# 2WiresLink_BluePill.net
KiCad netlist of a schematic drawn in EAGLE
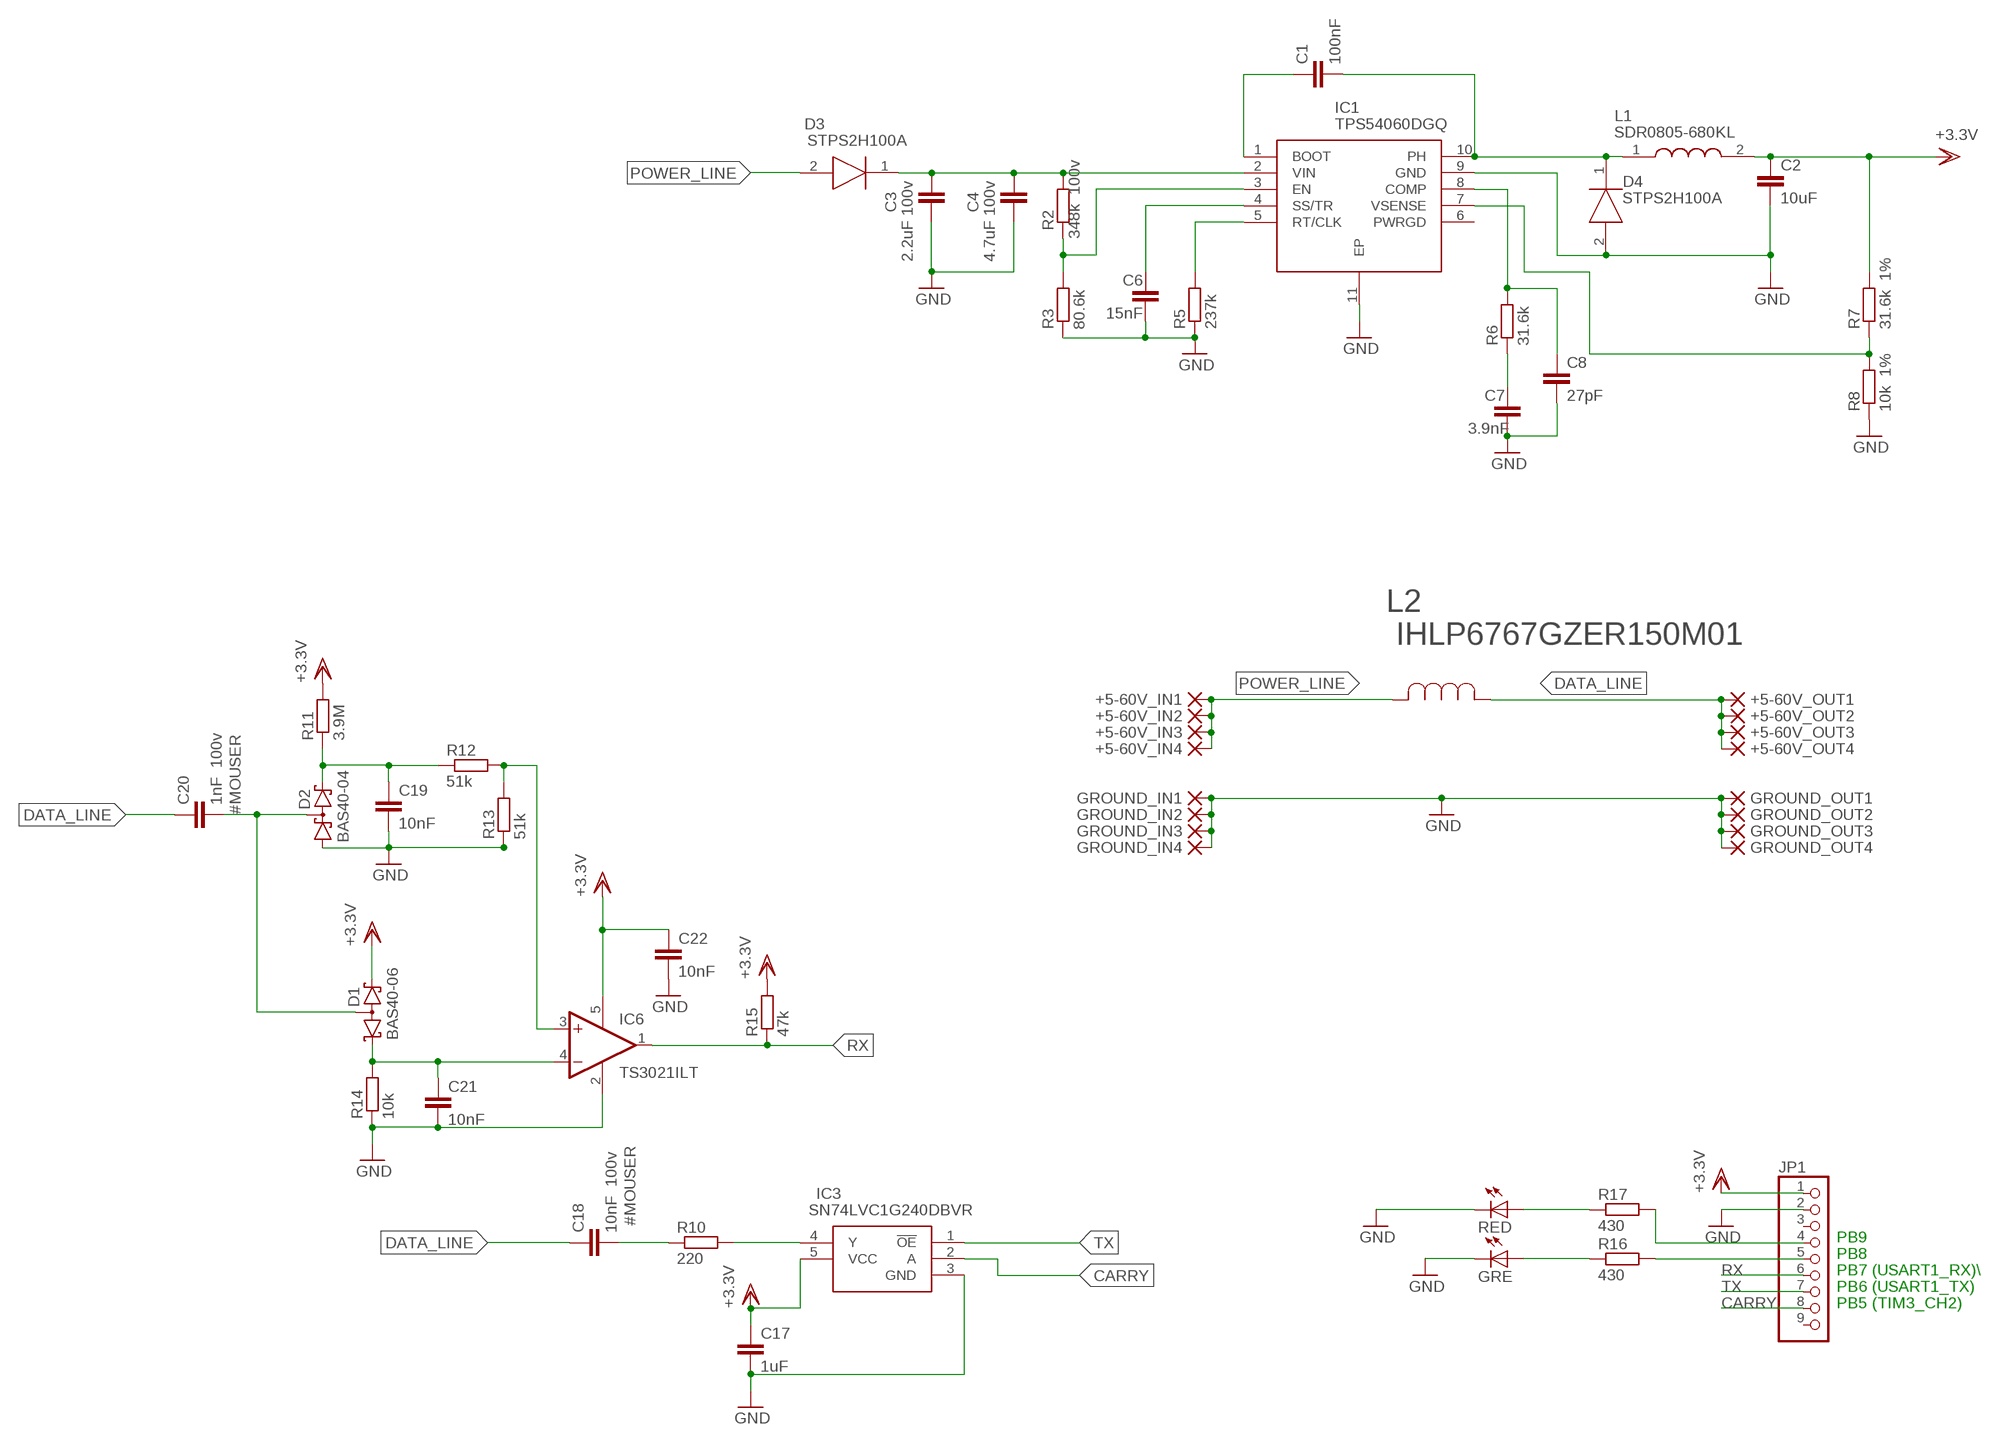
[diagram p0: schematic, sheet 1]

(export (version "E")
  (design (tool "Eeschema 10.0.6"))
  (components
    (comp (ref "+5-60V_IN1")
      (value "PAD-0820-S")
      (footprint "eagle-import:0820-S")
      (libsource (lib "eagle-import") (part "PAD-0820-S"))
    )
    (comp (ref "+5-60V_IN2")
      (value "PAD-0820-S")
      (footprint "eagle-import:0820-S")
      (libsource (lib "eagle-import") (part "PAD-0820-S"))
    )
    (comp (ref "+5-60V_IN3")
      (value "PAD-0820-S")
      (footprint "eagle-import:0820-S")
      (libsource (lib "eagle-import") (part "PAD-0820-S"))
    )
    (comp (ref "+5-60V_IN4")
      (value "PAD-0820-S")
      (footprint "eagle-import:0820-S")
      (libsource (lib "eagle-import") (part "PAD-0820-S"))
    )
    (comp (ref "+5-60V_OUT1")
      (value "PAD-0820-S")
      (footprint "eagle-import:0820-S")
      (libsource (lib "eagle-import") (part "PAD-0820-S"))
    )
    (comp (ref "+5-60V_OUT2")
      (value "PAD-0820-S")
      (footprint "eagle-import:0820-S")
      (libsource (lib "eagle-import") (part "PAD-0820-S"))
    )
    (comp (ref "+5-60V_OUT3")
      (value "PAD-0820-S")
      (footprint "eagle-import:0820-S")
      (libsource (lib "eagle-import") (part "PAD-0820-S"))
    )
    (comp (ref "+5-60V_OUT4")
      (value "PAD-0820-S")
      (footprint "eagle-import:0820-S")
      (libsource (lib "eagle-import") (part "PAD-0820-S"))
    )
    (comp (ref "C1")
      (value "100nF")
      (footprint "eagle-import:C0603")
      (fields (field (name "MF") "KEMET") (field (name "MPN") "C0603C104K5RECAUTO"))
      (libsource (lib "eagle-import") (part "C-EUC0603"))
    )
    (comp (ref "C2")
      (value "10uF")
      (footprint "eagle-import:C0603")
      (fields (field (name "MF") "Murata Electronics") (field (name "MPN") "GRM188R61A106KE69D"))
      (libsource (lib "eagle-import") (part "C-EUC0603"))
    )
    (comp (ref "C3")
      (value "2.2uF 100v")
      (footprint "eagle-import:C1210")
      (fields (field (name "MF") "TDK") (field (name "MPN") "C3225X7R2A225K230AB"))
      (libsource (lib "eagle-import") (part "C-EUC1210"))
    )
    (comp (ref "C4")
      (value "4.7uF 100v")
      (footprint "eagle-import:C1210")
      (fields (field (name "MF") "TDK") (field (name "MPN") "CGA6M3X7S2A475K200AB"))
      (libsource (lib "eagle-import") (part "C-EUC1210"))
    )
    (comp (ref "C6")
      (value "15nF")
      (footprint "eagle-import:C0603")
      (fields (field (name "MF") "KEMET") (field (name "MPN") "C0603C153K5RACTU"))
      (libsource (lib "eagle-import") (part "C-EUC0603"))
    )
    (comp (ref "C7")
      (value "3.9nF")
      (footprint "eagle-import:C0603")
      (fields (field (name "MF") "Murata Electronics") (field (name "MPN") "GCM1885C1H392JA16D"))
      (libsource (lib "eagle-import") (part "C-EUC0603"))
    )
    (comp (ref "C8")
      (value "27pF")
      (footprint "eagle-import:C0603")
      (fields (field (name "MF") "AVX") (field (name "MPN") "06035A270JAT2A"))
      (libsource (lib "eagle-import") (part "C-EUC0603"))
    )
    (comp (ref "C17")
      (value "1uF")
      (footprint "eagle-import:C0603")
      (fields (field (name "MF") "AVX") (field (name "MPN") "0603YD105KAT2A"))
      (libsource (lib "eagle-import") (part "C-EUC0603"))
    )
    (comp (ref "C18")
      (value "10nF 100v")
      (footprint "eagle-import:C0603")
      (fields (field (name "MF") "Murata Electronics") (field (name "MPN") "GCM188R72A103KA37D"))
      (libsource (lib "eagle-import") (part "C-EUC0603"))
    )
    (comp (ref "C19")
      (value "10nF")
      (footprint "eagle-import:C0603")
      (fields (field (name "MF") "KEMET") (field (name "MPN") "C0603C103K5RACAUTO7411"))
      (libsource (lib "eagle-import") (part "C-EUC0603"))
    )
    (comp (ref "C20")
      (value "1nF 100v")
      (footprint "eagle-import:C0603")
      (fields (field (name "MF") "AVX") (field (name "MPN") "06031C102KAT2A"))
      (libsource (lib "eagle-import") (part "C-EUC0603"))
    )
    (comp (ref "C21")
      (value "10nF")
      (footprint "eagle-import:C0603")
      (fields (field (name "MF") "KEMET"))
      (libsource (lib "eagle-import") (part "C-EUC0603"))
    )
    (comp (ref "C22")
      (value "10nF")
      (footprint "eagle-import:C0603")
      (fields (field (name "MF") "KEMET") (field (name "MPN") "C0603C103K5RACAUTO7411"))
      (libsource (lib "eagle-import") (part "C-EUC0603"))
    )
    (comp (ref "D1")
      (value "BAS40-06")
      (footprint "eagle-import:SOT23")
      (fields (field (name "MF") "Vishay Semiconductors") (field (name "MPN") "BAS40-06-E3-08"))
      (libsource (lib "eagle-import") (part "BAS40-06"))
    )
    (comp (ref "D2")
      (value "BAS40-04")
      (footprint "eagle-import:SOT23")
      (fields (field (name "MF") "Diodes Incorporated") (field (name "MPN") "BAS40-04-7-F"))
      (libsource (lib "eagle-import") (part "BAS40-04"))
    )
    (comp (ref "D3")
      (value "STPS2H100A")
      (footprint "eagle-import:DIOM5126X265N")
      (fields (field (name "MOUSER_PART_NUMBER") "511-STPS2H100A") (field (name "MF") "STMicroelectronics"))
      (libsource (lib "eagle-import") (part "STPS2H100A"))
    )
    (comp (ref "D4")
      (value "STPS2H100A")
      (footprint "eagle-import:DIOM5126X265N")
      (fields (field (name "MOUSER_PART_NUMBER") "511-STPS2H100A") (field (name "MF") "STMicroelectronics"))
      (libsource (lib "eagle-import") (part "STPS2H100A"))
    )
    (comp (ref "GRE")
      (value "GRE")
      (footprint "eagle-import:CHIP-LED0805")
      (fields (field (name "MF") "Lumex") (field (name "MPN") "SML-LXT0805GW-TR"))
      (libsource (lib "eagle-import") (part "LEDCHIP-LED0805"))
    )
    (comp (ref "GROUND_IN1")
      (value "PAD-0820-S")
      (footprint "eagle-import:0820-S")
      (libsource (lib "eagle-import") (part "PAD-0820-S"))
    )
    (comp (ref "GROUND_IN2")
      (value "PAD-0820-S")
      (footprint "eagle-import:0820-S")
      (libsource (lib "eagle-import") (part "PAD-0820-S"))
    )
    (comp (ref "GROUND_IN3")
      (value "PAD-0820-S")
      (footprint "eagle-import:0820-S")
      (libsource (lib "eagle-import") (part "PAD-0820-S"))
    )
    (comp (ref "GROUND_IN4")
      (value "PAD-0820-S")
      (footprint "eagle-import:0820-S")
      (libsource (lib "eagle-import") (part "PAD-0820-S"))
    )
    (comp (ref "GROUND_OUT1")
      (value "PAD-0820-S")
      (footprint "eagle-import:0820-S")
      (libsource (lib "eagle-import") (part "PAD-0820-S"))
    )
    (comp (ref "GROUND_OUT2")
      (value "PAD-0820-S")
      (footprint "eagle-import:0820-S")
      (libsource (lib "eagle-import") (part "PAD-0820-S"))
    )
    (comp (ref "GROUND_OUT3")
      (value "PAD-0820-S")
      (footprint "eagle-import:0820-S")
      (libsource (lib "eagle-import") (part "PAD-0820-S"))
    )
    (comp (ref "GROUND_OUT4")
      (value "PAD-0820-S")
      (footprint "eagle-import:0820-S")
      (libsource (lib "eagle-import") (part "PAD-0820-S"))
    )
    (comp (ref "IC1")
      (value "TPS54060DGQ")
      (footprint "eagle-import:SOP50P490X110-11N")
      (fields
        (field (name "MOUSER_PART_NUMBER") "595-TPS54060DGQ")
        (field (name "MF") "Texas Instruments")
        (field (name "MPN") "TPS54060DGQR")
      )
      (libsource (lib "eagle-import") (part "TPS54060DGQ"))
    )
    (comp (ref "IC3")
      (value "SN74LVC1G240DBVR")
      (footprint "eagle-import:SOT95P280X145-5N")
      (fields
        (field (name "MOUSER_PART_NUMBER") "595-SN74LVC1G240DBVR")
        (field (name "MF") "Texas Instruments")
      )
      (libsource (lib "eagle-import") (part "SN74LVC1G240DBVR"))
    )
    (comp (ref "IC6")
      (value "TS3021ILT")
      (footprint "eagle-import:SOT95P280X145-5N")
      (fields (field (name "MF") "STMicroelectronics"))
      (libsource (lib "eagle-import") (part "TS3021ILT"))
    )
    (comp (ref "JP1")
      (value "PINHD-1X9")
      (footprint "eagle-import:1X09-BIG")
      (libsource (lib "eagle-import") (part "PINHD-1X9"))
    )
    (comp (ref "L1")
      (value "SDR0805-680KL")
      (footprint "eagle-import:SDR0805-680KL")
      (fields (field (name "MOUSER_PART_NUMBER") "652-SDR0805-680KL") (field (name "MF") "Bourns"))
      (libsource (lib "eagle-import") (part "SDR0805-680KL"))
    )
    (comp (ref "L2")
      (value "IHLP6767GZER150M01")
      (footprint "eagle-import:IND_IHLP-6767GZ")
      (fields (field (name "MF") "Vishay / Dale"))
      (libsource (lib "eagle-import") (part "IHLP6767GZER150M01"))
    )
    (comp (ref "R2")
      (value "348k 100v")
      (footprint "eagle-import:R0603")
      (fields (field (name "MF") "Susumu") (field (name "MPN") "RG1608P-3483-D-T5"))
      (libsource (lib "eagle-import") (part "R-EU_R0603"))
    )
    (comp (ref "R3")
      (value "80.6k")
      (footprint "eagle-import:R0603")
      (fields (field (name "MF") "Vishay / Dale") (field (name "MPN") "CRCW060380K6FKEA"))
      (libsource (lib "eagle-import") (part "R-EU_R0603"))
    )
    (comp (ref "R5")
      (value "237k")
      (footprint "eagle-import:R0603")
      (fields (field (name "MF") "Yageo") (field (name "MPN") "AC0603FR-07237KL"))
      (libsource (lib "eagle-import") (part "R-EU_R0603"))
    )
    (comp (ref "R6")
      (value "31.6k")
      (footprint "eagle-import:R0603")
      (fields (field (name "MF") "Yageo") (field (name "MPN") "AC0603FR-0731K6L"))
      (libsource (lib "eagle-import") (part "R-EU_R0603"))
    )
    (comp (ref "R7")
      (value "31.6k 1%")
      (footprint "eagle-import:R0603")
      (fields (field (name "MF") "Yageo") (field (name "MPN") "AC0603FR-0731K6L"))
      (libsource (lib "eagle-import") (part "R-EU_R0603"))
    )
    (comp (ref "R8")
      (value "10k 1%")
      (footprint "eagle-import:R0603")
      (fields (field (name "MF") "Vishay / Dale") (field (name "MPN") "CRCW060310K0FKEAC"))
      (libsource (lib "eagle-import") (part "R-EU_R0603"))
    )
    (comp (ref "R10")
      (value "220")
      (footprint "eagle-import:R0603")
      (fields (field (name "MF") "Yageo") (field (name "MPN") "RC0603FR-07220RL"))
      (libsource (lib "eagle-import") (part "R-EU_R0603"))
    )
    (comp (ref "R11")
      (value "3.9M")
      (footprint "eagle-import:R0603")
      (fields (field (name "MF") "Yageo") (field (name "MPN") "RC0603FR-073M9L"))
      (libsource (lib "eagle-import") (part "R-EU_R0603"))
    )
    (comp (ref "R12")
      (value "51k")
      (footprint "eagle-import:R0603")
      (fields (field (name "MF") "Yageo") (field (name "MPN") "RC0603FR-0751KL"))
      (libsource (lib "eagle-import") (part "R-EU_R0603"))
    )
    (comp (ref "R13")
      (value "51k")
      (footprint "eagle-import:R0603")
      (fields (field (name "MF") "Yageo") (field (name "MPN") "RC0603FR-0751KL"))
      (libsource (lib "eagle-import") (part "R-EU_R0603"))
    )
    (comp (ref "R14")
      (value "10k")
      (footprint "eagle-import:R0603")
      (fields (field (name "MF") "Vishay / Dale") (field (name "MPN") "CRCW060310K0FKEAC"))
      (libsource (lib "eagle-import") (part "R-EU_R0603"))
    )
    (comp (ref "R15")
      (value "47k")
      (footprint "eagle-import:R0603")
      (fields (field (name "MF") "Yageo") (field (name "MPN") "RC0603FR-0747KL"))
      (libsource (lib "eagle-import") (part "R-EU_R0603"))
    )
    (comp (ref "R16")
      (value "430")
      (footprint "eagle-import:R0603")
      (fields (field (name "MF") "Yageo") (field (name "MPN") "RC0603FR-07430RL"))
      (libsource (lib "eagle-import") (part "R-EU_R0603"))
    )
    (comp (ref "R17")
      (value "430")
      (footprint "eagle-import:R0603")
      (fields (field (name "MF") "Yageo") (field (name "MPN") "RC0603FR-07430RL"))
      (libsource (lib "eagle-import") (part "R-EU_R0603"))
    )
    (comp (ref "RED")
      (value "RED")
      (footprint "eagle-import:CHIP-LED0805")
      (fields (field (name "MF") "Lumex") (field (name "MPN") "SML-LXT0805IW-TR"))
      (libsource (lib "eagle-import") (part "LEDCHIP-LED0805"))
    )
  )
  (nets
    (net (code "1") (name "+3.3V") (class "Default")
      (node (ref "C17") (pin "1") (pinfunction "1_1") (pintype "passive"))
      (node (ref "C2") (pin "1") (pinfunction "1_1") (pintype "passive"))
      (node (ref "C22") (pin "1") (pinfunction "1_1") (pintype "passive"))
      (node (ref "D1") (pin "2") (pinfunction "K2_2") (pintype "passive"))
      (node (ref "IC3") (pin "5") (pinfunction "VCC_5") (pintype "power_in"))
      (node (ref "IC6") (pin "5") (pinfunction "V+_5") (pintype "power_in"))
      (node (ref "JP1") (pin "1") (pinfunction "1_1") (pintype "passive"))
      (node (ref "L1") (pin "2") (pinfunction "2_2") (pintype "bidirectional"))
      (node (ref "R11") (pin "2") (pinfunction "2_2") (pintype "passive"))
      (node (ref "R15") (pin "2") (pinfunction "2_2") (pintype "passive"))
      (node (ref "R7") (pin "2") (pinfunction "2_2") (pintype "passive"))
    )
    (net (code "2") (name "CARRY") (class "Default")
      (node (ref "IC3") (pin "2") (pinfunction "A_2") (pintype "input"))
      (node (ref "JP1") (pin "8") (pinfunction "8_8") (pintype "passive"))
    )
    (net (code "3") (name "DATA_LINE") (class "Default")
      (node (ref "+5-60V_OUT1") (pin "P$1") (pinfunction "P_P$1") (pintype "passive"))
      (node (ref "+5-60V_OUT2") (pin "P$1") (pinfunction "P_P$1") (pintype "passive"))
      (node (ref "+5-60V_OUT3") (pin "P$1") (pinfunction "P_P$1") (pintype "passive"))
      (node (ref "+5-60V_OUT4") (pin "P$1") (pinfunction "P_P$1") (pintype "passive"))
      (node (ref "C18") (pin "1") (pinfunction "1_1") (pintype "passive"))
      (node (ref "C20") (pin "1") (pinfunction "1_1") (pintype "passive"))
      (node (ref "L2") (pin "1") (pinfunction "1_1") (pintype "passive"))
    )
    (net (code "4") (name "GND") (class "Default")
      (node (ref "C17") (pin "2") (pinfunction "2_2") (pintype "passive"))
      (node (ref "C19") (pin "2") (pinfunction "2_2") (pintype "passive"))
      (node (ref "C2") (pin "2") (pinfunction "2_2") (pintype "passive"))
      (node (ref "C21") (pin "2") (pinfunction "2_2") (pintype "passive"))
      (node (ref "C22") (pin "2") (pinfunction "2_2") (pintype "passive"))
      (node (ref "C3") (pin "2") (pinfunction "2_2") (pintype "passive"))
      (node (ref "C4") (pin "2") (pinfunction "2_2") (pintype "passive"))
      (node (ref "C6") (pin "2") (pinfunction "2_2") (pintype "passive"))
      (node (ref "C7") (pin "2") (pinfunction "2_2") (pintype "passive"))
      (node (ref "C8") (pin "2") (pinfunction "2_2") (pintype "passive"))
      (node (ref "D2") (pin "1") (pinfunction "A1_1") (pintype "passive"))
      (node (ref "D4") (pin "2") (pinfunction "A_2") (pintype "bidirectional"))
      (node (ref "GRE") (pin "C") (pinfunction "C_C") (pintype "passive"))
      (node (ref "GROUND_IN1") (pin "P$1") (pinfunction "P_P$1") (pintype "passive"))
      (node (ref "GROUND_IN2") (pin "P$1") (pinfunction "P_P$1") (pintype "passive"))
      (node (ref "GROUND_IN3") (pin "P$1") (pinfunction "P_P$1") (pintype "passive"))
      (node (ref "GROUND_IN4") (pin "P$1") (pinfunction "P_P$1") (pintype "passive"))
      (node (ref "GROUND_OUT1") (pin "P$1") (pinfunction "P_P$1") (pintype "passive"))
      (node (ref "GROUND_OUT2") (pin "P$1") (pinfunction "P_P$1") (pintype "passive"))
      (node (ref "GROUND_OUT3") (pin "P$1") (pinfunction "P_P$1") (pintype "passive"))
      (node (ref "GROUND_OUT4") (pin "P$1") (pinfunction "P_P$1") (pintype "passive"))
      (node (ref "IC1") (pin "11") (pinfunction "EP_11") (pintype "power_in"))
      (node (ref "IC1") (pin "9") (pinfunction "GND_9") (pintype "power_in"))
      (node (ref "IC3") (pin "3") (pinfunction "GND_3") (pintype "power_in"))
      (node (ref "IC6") (pin "2") (pinfunction "V-_2") (pintype "power_in"))
      (node (ref "JP1") (pin "2") (pinfunction "2_2") (pintype "passive"))
      (node (ref "R13") (pin "1") (pinfunction "1_1") (pintype "passive"))
      (node (ref "R14") (pin "1") (pinfunction "1_1") (pintype "passive"))
      (node (ref "R3") (pin "1") (pinfunction "1_1") (pintype "passive"))
      (node (ref "R5") (pin "1") (pinfunction "1_1") (pintype "passive"))
      (node (ref "R8") (pin "1") (pinfunction "1_1") (pintype "passive"))
      (node (ref "RED") (pin "C") (pinfunction "C_C") (pintype "passive"))
    )
    (net (code "5") (name "Net-(C7-Pad1)") (class "Default")
      (node (ref "C7") (pin "1") (pinfunction "1_1") (pintype "passive"))
      (node (ref "R6") (pin "1") (pinfunction "1_1") (pintype "passive"))
    )
    (net (code "6") (name "Net-(C18-Pad2)") (class "Default")
      (node (ref "C18") (pin "2") (pinfunction "2_2") (pintype "passive"))
      (node (ref "R10") (pin "1") (pinfunction "1_1") (pintype "passive"))
    )
    (net (code "7") (name "Net-(D1-AA)") (class "Default")
      (node (ref "C20") (pin "2") (pinfunction "2_2") (pintype "passive"))
      (node (ref "D1") (pin "3") (pinfunction "AA_3") (pintype "passive"))
      (node (ref "D2") (pin "3") (pinfunction "C1A2_3") (pintype "passive"))
    )
    (net (code "8") (name "Net-(D1-K1)") (class "Default")
      (node (ref "C21") (pin "1") (pinfunction "1_1") (pintype "passive"))
      (node (ref "D1") (pin "1") (pinfunction "K1_1") (pintype "passive"))
      (node (ref "IC6") (pin "4") (pinfunction "-IN_4") (pintype "input"))
      (node (ref "R14") (pin "2") (pinfunction "2_2") (pintype "passive"))
    )
    (net (code "9") (name "Net-(D2-C2)") (class "Default")
      (node (ref "C19") (pin "1") (pinfunction "1_1") (pintype "passive"))
      (node (ref "D2") (pin "2") (pinfunction "C2_2") (pintype "passive"))
      (node (ref "R11") (pin "1") (pinfunction "1_1") (pintype "passive"))
      (node (ref "R12") (pin "1") (pinfunction "1_1") (pintype "passive"))
    )
    (net (code "10") (name "Net-(D3-K)") (class "Default")
      (node (ref "C3") (pin "1") (pinfunction "1_1") (pintype "passive"))
      (node (ref "C4") (pin "1") (pinfunction "1_1") (pintype "passive"))
      (node (ref "D3") (pin "1") (pinfunction "K_1") (pintype "bidirectional"))
      (node (ref "IC1") (pin "2") (pinfunction "VIN_2") (pintype "input"))
      (node (ref "R2") (pin "2") (pinfunction "2_2") (pintype "passive"))
    )
    (net (code "11") (name "Net-(D4-K)") (class "Default")
      (node (ref "C1") (pin "2") (pinfunction "2_2") (pintype "passive"))
      (node (ref "D4") (pin "1") (pinfunction "K_1") (pintype "bidirectional"))
      (node (ref "IC1") (pin "10") (pinfunction "PH_10") (pintype "bidirectional"))
      (node (ref "L1") (pin "1") (pinfunction "1_1") (pintype "bidirectional"))
    )
    (net (code "12") (name "Net-(GRE-PadA)") (class "Default")
      (node (ref "GRE") (pin "A") (pinfunction "A_A") (pintype "passive"))
      (node (ref "R16") (pin "1") (pinfunction "1_1") (pintype "passive"))
    )
    (net (code "13") (name "Net-(IC1-BOOT)") (class "Default")
      (node (ref "C1") (pin "1") (pinfunction "1_1") (pintype "passive"))
      (node (ref "IC1") (pin "1") (pinfunction "BOOT_1") (pintype "bidirectional"))
    )
    (net (code "14") (name "Net-(IC1-COMP)") (class "Default")
      (node (ref "C8") (pin "1") (pinfunction "1_1") (pintype "passive"))
      (node (ref "IC1") (pin "8") (pinfunction "COMP_8") (pintype "bidirectional"))
      (node (ref "R6") (pin "2") (pinfunction "2_2") (pintype "passive"))
    )
    (net (code "15") (name "Net-(IC1-EN)") (class "Default")
      (node (ref "IC1") (pin "3") (pinfunction "EN_3") (pintype "bidirectional"))
      (node (ref "R2") (pin "1") (pinfunction "1_1") (pintype "passive"))
      (node (ref "R3") (pin "2") (pinfunction "2_2") (pintype "passive"))
    )
    (net (code "16") (name "Net-(IC1-RT{slash}CLK)") (class "Default")
      (node (ref "IC1") (pin "5") (pinfunction "RT/CLK_5") (pintype "input"))
      (node (ref "R5") (pin "2") (pinfunction "2_2") (pintype "passive"))
    )
    (net (code "17") (name "Net-(IC1-SS{slash}TR)") (class "Default")
      (node (ref "C6") (pin "1") (pinfunction "1_1") (pintype "passive"))
      (node (ref "IC1") (pin "4") (pinfunction "SS/TR_4") (pintype "bidirectional"))
    )
    (net (code "18") (name "Net-(IC1-VSENSE)") (class "Default")
      (node (ref "IC1") (pin "7") (pinfunction "VSENSE_7") (pintype "bidirectional"))
      (node (ref "R7") (pin "1") (pinfunction "1_1") (pintype "passive"))
      (node (ref "R8") (pin "2") (pinfunction "2_2") (pintype "passive"))
    )
    (net (code "19") (name "Net-(IC3-Y)") (class "Default")
      (node (ref "IC3") (pin "4") (pinfunction "Y_4") (pintype "output"))
      (node (ref "R10") (pin "2") (pinfunction "2_2") (pintype "passive"))
    )
    (net (code "20") (name "Net-(IC6-+IN)") (class "Default")
      (node (ref "IC6") (pin "3") (pinfunction "+IN_3") (pintype "input"))
      (node (ref "R12") (pin "2") (pinfunction "2_2") (pintype "passive"))
      (node (ref "R13") (pin "2") (pinfunction "2_2") (pintype "passive"))
    )
    (net (code "21") (name "Net-(JP1-Pad4)") (class "Default")
      (node (ref "JP1") (pin "4") (pinfunction "4_4") (pintype "passive"))
      (node (ref "R17") (pin "2") (pinfunction "2_2") (pintype "passive"))
    )
    (net (code "22") (name "Net-(JP1-Pad5)") (class "Default")
      (node (ref "JP1") (pin "5") (pinfunction "5_5") (pintype "passive"))
      (node (ref "R16") (pin "2") (pinfunction "2_2") (pintype "passive"))
    )
    (net (code "23") (name "Net-(R17-Pad1)") (class "Default")
      (node (ref "R17") (pin "1") (pinfunction "1_1") (pintype "passive"))
      (node (ref "RED") (pin "A") (pinfunction "A_A") (pintype "passive"))
    )
    (net (code "24") (name "POWER_LINE") (class "Default")
      (node (ref "+5-60V_IN1") (pin "P$1") (pinfunction "P_P$1") (pintype "passive"))
      (node (ref "+5-60V_IN2") (pin "P$1") (pinfunction "P_P$1") (pintype "passive"))
      (node (ref "+5-60V_IN3") (pin "P$1") (pinfunction "P_P$1") (pintype "passive"))
      (node (ref "+5-60V_IN4") (pin "P$1") (pinfunction "P_P$1") (pintype "passive"))
      (node (ref "D3") (pin "2") (pinfunction "A_2") (pintype "bidirectional"))
      (node (ref "L2") (pin "2") (pinfunction "2_2") (pintype "passive"))
    )
    (net (code "25") (name "RX") (class "Default")
      (node (ref "IC6") (pin "1") (pinfunction "OUT_1") (pintype "output"))
      (node (ref "JP1") (pin "6") (pinfunction "6_6") (pintype "passive"))
      (node (ref "R15") (pin "1") (pinfunction "1_1") (pintype "passive"))
    )
    (net (code "26") (name "TX") (class "Default")
      (node (ref "IC3") (pin "1") (pinfunction "~{OE}_1") (pintype "input"))
      (node (ref "JP1") (pin "7") (pinfunction "7_7") (pintype "passive"))
    )
    (net (code "27") (name "unconnected-(IC1-PWRGD-Pad6)") (class "Default")
      (node (ref "IC1") (pin "6") (pinfunction "PWRGD_6") (pintype "bidirectional"))
    )
    (net (code "28") (name "unconnected-(JP1-Pad3)") (class "Default")
      (node (ref "JP1") (pin "3") (pinfunction "3_3") (pintype "passive"))
    )
    (net (code "29") (name "unconnected-(JP1-Pad9)") (class "Default")
      (node (ref "JP1") (pin "9") (pinfunction "9_9") (pintype "passive"))
    )
  )
)
